# ap_hand_controller_v2.net
KiCad netlist of a schematic drawn in EAGLE
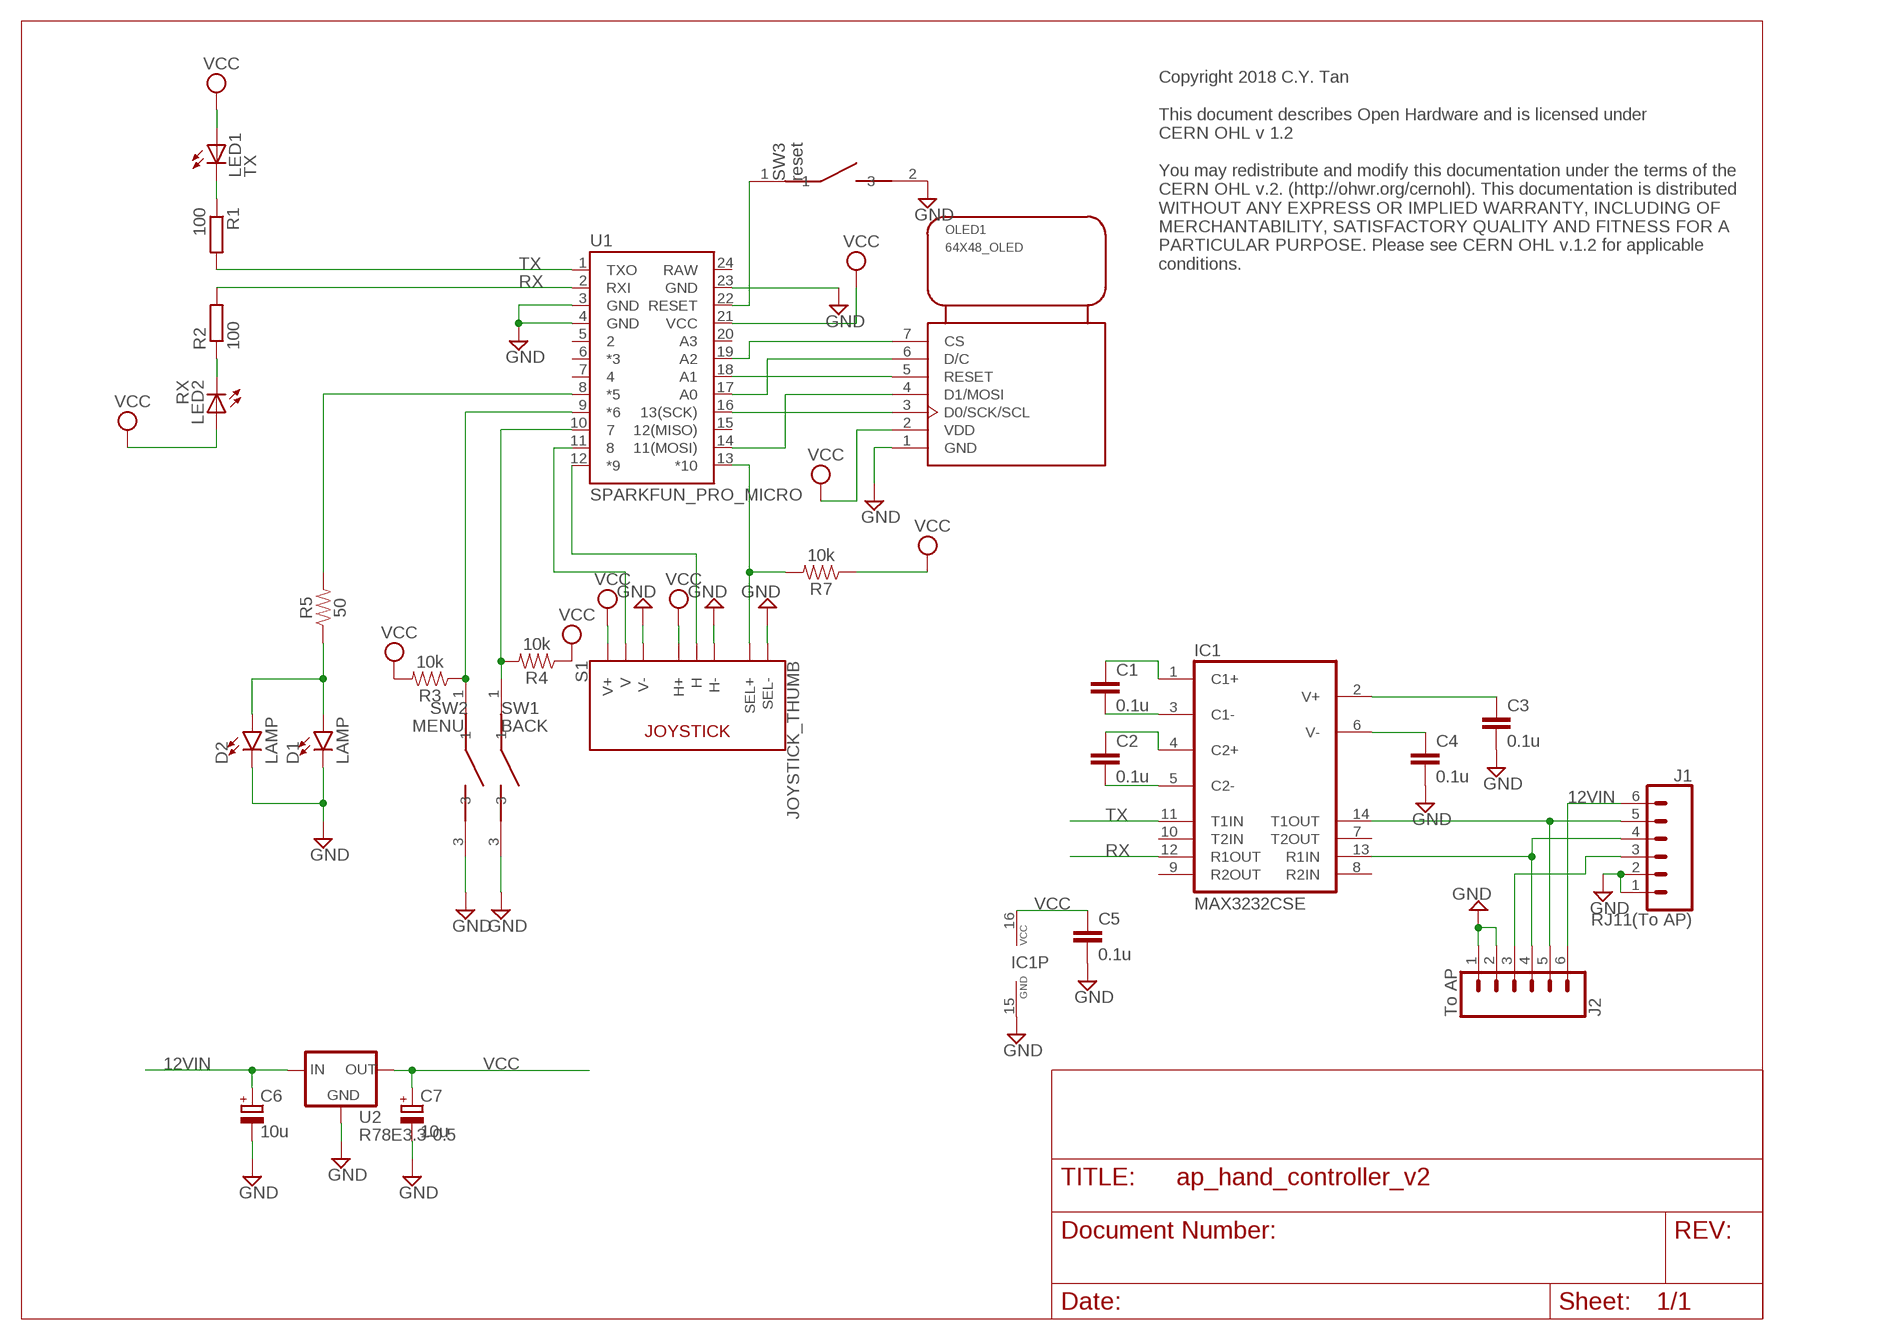
[diagram p0: schematic, sheet 1]

(export (version "E")
  (design (tool "Eeschema 10.0.6"))
  (components
    (comp (ref "C1")
      (value "0.1u")
      (footprint "eagle-import:C1206")
      (libsource (lib "eagle-import") (part "C-EUC1206"))
    )
    (comp (ref "C2")
      (value "0.1u")
      (footprint "eagle-import:C1206")
      (libsource (lib "eagle-import") (part "C-EUC1206"))
    )
    (comp (ref "C3")
      (value "0.1u")
      (footprint "eagle-import:C1206")
      (libsource (lib "eagle-import") (part "C-EUC1206"))
    )
    (comp (ref "C4")
      (value "0.1u")
      (footprint "eagle-import:C1206")
      (libsource (lib "eagle-import") (part "C-EUC1206"))
    )
    (comp (ref "C5")
      (value "0.1u")
      (footprint "eagle-import:C1206")
      (libsource (lib "eagle-import") (part "C-EUC1206"))
    )
    (comp (ref "C6")
      (value "10u")
      (footprint "eagle-import:E2,5-6")
      (libsource (lib "eagle-import") (part "CPOL-EUE2.5-6"))
    )
    (comp (ref "C7")
      (value "10u")
      (footprint "eagle-import:E2,5-6")
      (libsource (lib "eagle-import") (part "CPOL-EUE2.5-6"))
    )
    (comp (ref "D1")
      (value "LAMP")
      (footprint "eagle-import:LED_5MM")
      (libsource (lib "eagle-import") (part "LED5MM"))
    )
    (comp (ref "D2")
      (value "LAMP")
      (footprint "eagle-import:LED_5MM")
      (libsource (lib "eagle-import") (part "LED5MM"))
    )
    (comp (ref "IC1")
      (value "MAX3232CSE")
      (footprint "eagle-import:SO16")
      (libsource (lib "eagle-import") (part "MAX3232SEC"))
    )
    (comp (ref "J1")
      (value "RJ11(To AP)")
      (footprint "eagle-import:RJ11-6")
      (libsource (lib "eagle-import") (part "RJ11-6"))
    )
    (comp (ref "J2")
      (value "To AP")
      (footprint "eagle-import:1X06_NO_SILK")
      (libsource (lib "eagle-import") (part "CONN_06NO_SILK_FEMALE_PTH"))
    )
    (comp (ref "LED1")
      (value "TX")
      (footprint "eagle-import:CHIPLED_1206")
      (libsource (lib "eagle-import") (part "LEDCHIPLED_1206"))
    )
    (comp (ref "LED2")
      (value "RX")
      (footprint "eagle-import:CHIPLED_1206")
      (libsource (lib "eagle-import") (part "LEDCHIPLED_1206"))
    )
    (comp (ref "OLED1")
      (value "64X48_OLED")
      (footprint "eagle-import:64X48_OLED")
      (libsource (lib "eagle-import") (part "64X48_OLED"))
    )
    (comp (ref "R1")
      (value "100")
      (footprint "eagle-import:R0805")
      (libsource (lib "eagle-import") (part "R"))
    )
    (comp (ref "R2")
      (value "100")
      (footprint "eagle-import:R0805")
      (libsource (lib "eagle-import") (part "R"))
    )
    (comp (ref "R3")
      (value "10k")
      (footprint "eagle-import:AXIAL-0.3")
      (libsource (lib "eagle-import") (part "RESISTORAXIAL-0.3"))
    )
    (comp (ref "R4")
      (value "10k")
      (footprint "eagle-import:AXIAL-0.3")
      (libsource (lib "eagle-import") (part "RESISTORAXIAL-0.3"))
    )
    (comp (ref "R5")
      (value "50")
      (footprint "eagle-import:AXIAL-0.3")
      (libsource (lib "eagle-import") (part "RESISTORAXIAL-0.3"))
    )
    (comp (ref "R7")
      (value "10k")
      (footprint "eagle-import:AXIAL-0.3")
      (libsource (lib "eagle-import") (part "RESISTORAXIAL-0.3"))
    )
    (comp (ref "S1")
      (value "JOYSTICK_THUMB")
      (footprint "eagle-import:JOYSTICK")
      (libsource (lib "eagle-import") (part "JOYSTICK_THUMB"))
    )
    (comp (ref "SW1")
      (value "BACK")
      (footprint "eagle-import:TSA12110_TACT_SWITCH")
      (libsource (lib "eagle-import") (part "TSA12110_TACT_SWITCH"))
    )
    (comp (ref "SW2")
      (value "MENU")
      (footprint "eagle-import:TSA12110_TACT_SWITCH")
      (libsource (lib "eagle-import") (part "TSA12110_TACT_SWITCH"))
    )
    (comp (ref "SW3")
      (value "reset")
      (footprint "eagle-import:TACTILE_SWITCH_90DEG")
      (libsource (lib "eagle-import") (part "TACTILE_SWITCH_90DEG"))
    )
    (comp (ref "U1")
      (value "SPARKFUN_PRO_MICRO")
      (footprint "eagle-import:SPARKFUN_PRO_MICRO")
      (libsource (lib "eagle-import") (part "SPARKFUN_PRO_MICRO"))
    )
    (comp (ref "U2")
      (value "R78E3.3-0.5")
      (footprint "eagle-import:DC-DC_CONVERTER_78XX")
      (libsource (lib "eagle-import") (part "R-78E5.0-1.0"))
    )
  )
  (nets
    (net (code "1") (name "/12VIN") (class "Default")
      (node (ref "C6") (pin "+") (pinfunction "+_+") (pintype "passive"))
      (node (ref "J1") (pin "6") (pinfunction "6_6") (pintype "passive"))
      (node (ref "J2") (pin "6") (pinfunction "6_6") (pintype "passive"))
      (node (ref "U2") (pin "VIN") (pinfunction "IN_VIN") (pintype "input"))
    )
    (net (code "2") (name "/RAW") (class "Default")
      (node (ref "U1") (pin "24") (pinfunction "RAW_24") (pintype "power_in"))
    )
    (net (code "3") (name "/RX") (class "Default")
      (node (ref "IC1") (pin "12") (pinfunction "R1OUT_12") (pintype "output"))
      (node (ref "R2") (pin "2") (pinfunction "2_2") (pintype "passive"))
      (node (ref "U1") (pin "2") (pinfunction "RXI_2") (pintype "bidirectional"))
    )
    (net (code "4") (name "/TX") (class "Default")
      (node (ref "IC1") (pin "11") (pinfunction "T1IN_11") (pintype "input"))
      (node (ref "R1") (pin "2") (pinfunction "2_2") (pintype "passive"))
      (node (ref "U1") (pin "1") (pinfunction "TXO_1") (pintype "bidirectional"))
    )
    (net (code "5") (name "GND") (class "Default")
      (node (ref "C3") (pin "2") (pinfunction "2_2") (pintype "passive"))
      (node (ref "C4") (pin "2") (pinfunction "2_2") (pintype "passive"))
      (node (ref "C5") (pin "2") (pinfunction "2_2") (pintype "passive"))
      (node (ref "C6") (pin "-") (pinfunction "-_-") (pintype "passive"))
      (node (ref "C7") (pin "-") (pinfunction "-_-") (pintype "passive"))
      (node (ref "D1") (pin "K") (pinfunction "C_K") (pintype "passive"))
      (node (ref "D2") (pin "K") (pinfunction "C_K") (pintype "passive"))
      (node (ref "IC1") (pin "15") (pinfunction "GND_15") (pintype "power_in"))
      (node (ref "J1") (pin "1") (pinfunction "1_1") (pintype "passive"))
      (node (ref "J1") (pin "2") (pinfunction "2_2") (pintype "passive"))
      (node (ref "J2") (pin "1") (pinfunction "1_1") (pintype "passive"))
      (node (ref "J2") (pin "2") (pinfunction "2_2") (pintype "passive"))
      (node (ref "OLED1") (pin "1") (pinfunction "GND_1") (pintype "power_in"))
      (node (ref "S1") (pin "B2A") (pinfunction "SEL-_B2A") (pintype "bidirectional"))
      (node (ref "S1") (pin "H3") (pinfunction "H-_H3") (pintype "bidirectional"))
      (node (ref "S1") (pin "V3") (pinfunction "V-_V3") (pintype "bidirectional"))
      (node (ref "SW1") (pin "3") (pinfunction "3_3") (pintype "bidirectional"))
      (node (ref "SW2") (pin "3") (pinfunction "3_3") (pintype "bidirectional"))
      (node (ref "SW3") (pin "2") (pinfunction "3_2") (pintype "bidirectional"))
      (node (ref "U1") (pin "23") (pinfunction "GND_23") (pintype "power_in"))
      (node (ref "U1") (pin "3") (pinfunction "GND_3") (pintype "power_in"))
      (node (ref "U1") (pin "4") (pinfunction "GND_4") (pintype "power_in"))
      (node (ref "U2") (pin "GND") (pinfunction "GND_GND") (pintype "input"))
    )
    (net (code "6") (name "Net-(IC1A-C1+)") (class "Default")
      (node (ref "C1") (pin "1") (pinfunction "1_1") (pintype "passive"))
      (node (ref "IC1") (pin "1") (pinfunction "C1+_1") (pintype "bidirectional"))
    )
    (net (code "7") (name "Net-(IC1A-C1-)") (class "Default")
      (node (ref "C1") (pin "2") (pinfunction "2_2") (pintype "passive"))
      (node (ref "IC1") (pin "3") (pinfunction "C1-_3") (pintype "bidirectional"))
    )
    (net (code "8") (name "Net-(IC1A-C2+)") (class "Default")
      (node (ref "C2") (pin "1") (pinfunction "1_1") (pintype "passive"))
      (node (ref "IC1") (pin "4") (pinfunction "C2+_4") (pintype "bidirectional"))
    )
    (net (code "9") (name "Net-(IC1A-C2-)") (class "Default")
      (node (ref "C2") (pin "2") (pinfunction "2_2") (pintype "passive"))
      (node (ref "IC1") (pin "5") (pinfunction "C2-_5") (pintype "bidirectional"))
    )
    (net (code "10") (name "Net-(IC1A-R1IN)") (class "Default")
      (node (ref "IC1") (pin "13") (pinfunction "R1IN_13") (pintype "input"))
      (node (ref "J1") (pin "4") (pinfunction "4_4") (pintype "passive"))
      (node (ref "J2") (pin "4") (pinfunction "4_4") (pintype "passive"))
    )
    (net (code "11") (name "Net-(IC1A-T1OUT)") (class "Default")
      (node (ref "IC1") (pin "14") (pinfunction "T1OUT_14") (pintype "output"))
      (node (ref "J1") (pin "5") (pinfunction "5_5") (pintype "passive"))
      (node (ref "J2") (pin "5") (pinfunction "5_5") (pintype "passive"))
    )
    (net (code "12") (name "Net-(IC1A-V+)") (class "Default")
      (node (ref "C3") (pin "1") (pinfunction "1_1") (pintype "passive"))
      (node (ref "IC1") (pin "2") (pinfunction "V+_2") (pintype "bidirectional"))
    )
    (net (code "13") (name "Net-(IC1A-V-)") (class "Default")
      (node (ref "C4") (pin "1") (pinfunction "1_1") (pintype "passive"))
      (node (ref "IC1") (pin "6") (pinfunction "V-_6") (pintype "bidirectional"))
    )
    (net (code "14") (name "Net-(J1-Pad3)") (class "Default")
      (node (ref "J1") (pin "3") (pinfunction "3_3") (pintype "passive"))
      (node (ref "J2") (pin "3") (pinfunction "3_3") (pintype "passive"))
    )
    (net (code "15") (name "Net-(LED1-PadC)") (class "Default")
      (node (ref "LED1") (pin "C") (pinfunction "C_C") (pintype "passive"))
      (node (ref "R1") (pin "1") (pinfunction "1_1") (pintype "passive"))
    )
    (net (code "16") (name "Net-(LED2-PadC)") (class "Default")
      (node (ref "LED2") (pin "C") (pinfunction "C_C") (pintype "passive"))
      (node (ref "R2") (pin "1") (pinfunction "1_1") (pintype "passive"))
    )
    (net (code "17") (name "Net-(OLED1-CS)") (class "Default")
      (node (ref "OLED1") (pin "7") (pinfunction "CS_7") (pintype "input"))
      (node (ref "U1") (pin "19") (pinfunction "A2_19") (pintype "bidirectional"))
    )
    (net (code "18") (name "Net-(OLED1-D0{slash}SCK{slash}SCL)") (class "Default")
      (node (ref "OLED1") (pin "3") (pinfunction "D0/SCK/SCL_3") (pintype "input"))
      (node (ref "U1") (pin "16") (pinfunction "13(SCK)_16") (pintype "bidirectional"))
    )
    (net (code "19") (name "Net-(OLED1-D1{slash}MOSI)") (class "Default")
      (node (ref "OLED1") (pin "4") (pinfunction "D1/MOSI_4") (pintype "bidirectional"))
      (node (ref "U1") (pin "14") (pinfunction "11(MOSI)_14") (pintype "bidirectional"))
    )
    (net (code "20") (name "Net-(OLED1-D{slash}C)") (class "Default")
      (node (ref "OLED1") (pin "6") (pinfunction "D/C_6") (pintype "bidirectional"))
      (node (ref "U1") (pin "17") (pinfunction "A0_17") (pintype "bidirectional"))
    )
    (net (code "21") (name "Net-(OLED1-RESET)") (class "Default")
      (node (ref "OLED1") (pin "5") (pinfunction "RESET_5") (pintype "input"))
      (node (ref "U1") (pin "18") (pinfunction "A1_18") (pintype "bidirectional"))
    )
    (net (code "22") (name "Net-(R3-1)") (class "Default")
      (node (ref "R3") (pin "P$1") (pinfunction "1_P$1") (pintype "passive"))
      (node (ref "SW2") (pin "1") (pinfunction "1_1") (pintype "bidirectional"))
      (node (ref "U1") (pin "9") (pinfunction "*6_9") (pintype "bidirectional"))
    )
    (net (code "23") (name "Net-(R4-2)") (class "Default")
      (node (ref "R4") (pin "P$2") (pinfunction "2_P$2") (pintype "passive"))
      (node (ref "SW1") (pin "1") (pinfunction "1_1") (pintype "bidirectional"))
      (node (ref "U1") (pin "10") (pinfunction "7_10") (pintype "bidirectional"))
    )
    (net (code "24") (name "Net-(R5-1)") (class "Default")
      (node (ref "D1") (pin "A") (pinfunction "A_A") (pintype "passive"))
      (node (ref "D2") (pin "A") (pinfunction "A_A") (pintype "passive"))
      (node (ref "R5") (pin "P$1") (pinfunction "1_P$1") (pintype "passive"))
    )
    (net (code "25") (name "Net-(R5-2)") (class "Default")
      (node (ref "R5") (pin "P$2") (pinfunction "2_P$2") (pintype "passive"))
      (node (ref "U1") (pin "8") (pinfunction "*5_8") (pintype "bidirectional"))
    )
    (net (code "26") (name "Net-(R7-2)") (class "Default")
      (node (ref "R7") (pin "P$2") (pinfunction "2_P$2") (pintype "passive"))
      (node (ref "S1") (pin "B1A") (pinfunction "SEL+_B1A") (pintype "bidirectional"))
      (node (ref "U1") (pin "13") (pinfunction "*10_13") (pintype "bidirectional"))
    )
    (net (code "27") (name "Net-(S1-H)") (class "Default")
      (node (ref "S1") (pin "H2") (pinfunction "H_H2") (pintype "bidirectional"))
      (node (ref "U1") (pin "12") (pinfunction "*9_12") (pintype "bidirectional"))
    )
    (net (code "28") (name "Net-(S1-V)") (class "Default")
      (node (ref "S1") (pin "V2") (pinfunction "V_V2") (pintype "bidirectional"))
      (node (ref "U1") (pin "11") (pinfunction "8_11") (pintype "bidirectional"))
    )
    (net (code "29") (name "Net-(U1-RESET)") (class "Default")
      (node (ref "SW3") (pin "1") (pinfunction "1_1") (pintype "bidirectional"))
      (node (ref "U1") (pin "22") (pinfunction "RESET_22") (pintype "bidirectional"))
    )
    (net (code "30") (name "VCC") (class "Default")
      (node (ref "C5") (pin "1") (pinfunction "1_1") (pintype "passive"))
      (node (ref "C7") (pin "+") (pinfunction "+_+") (pintype "passive"))
      (node (ref "IC1") (pin "16") (pinfunction "VCC_16") (pintype "power_in"))
      (node (ref "LED1") (pin "A") (pinfunction "A_A") (pintype "passive"))
      (node (ref "LED2") (pin "A") (pinfunction "A_A") (pintype "passive"))
      (node (ref "OLED1") (pin "2") (pinfunction "VDD_2") (pintype "power_in"))
      (node (ref "R3") (pin "P$2") (pinfunction "2_P$2") (pintype "passive"))
      (node (ref "R4") (pin "P$1") (pinfunction "1_P$1") (pintype "passive"))
      (node (ref "R7") (pin "P$1") (pinfunction "1_P$1") (pintype "passive"))
      (node (ref "S1") (pin "H1") (pinfunction "H+_H1") (pintype "bidirectional"))
      (node (ref "S1") (pin "V1") (pinfunction "V+_V1") (pintype "bidirectional"))
      (node (ref "U1") (pin "21") (pinfunction "VCC_21") (pintype "power_in"))
      (node (ref "U2") (pin "VOUT") (pinfunction "OUT_VOUT") (pintype "passive"))
    )
    (net (code "31") (name "unconnected-(IC1A-R2IN-Pad8)") (class "Default")
      (node (ref "IC1") (pin "8") (pinfunction "R2IN_8") (pintype "input"))
    )
    (net (code "32") (name "unconnected-(IC1A-R2OUT-Pad9)") (class "Default")
      (node (ref "IC1") (pin "9") (pinfunction "R2OUT_9") (pintype "output"))
    )
    (net (code "33") (name "unconnected-(IC1A-T2IN-Pad10)") (class "Default")
      (node (ref "IC1") (pin "10") (pinfunction "T2IN_10") (pintype "input"))
    )
    (net (code "34") (name "unconnected-(IC1A-T2OUT-Pad7)") (class "Default")
      (node (ref "IC1") (pin "7") (pinfunction "T2OUT_7") (pintype "output"))
    )
    (net (code "35") (name "unconnected-(U1-*3-Pad6)") (class "Default")
      (node (ref "U1") (pin "6") (pinfunction "*3_6") (pintype "bidirectional"))
    )
    (net (code "36") (name "unconnected-(U1-2-Pad5)") (class "Default")
      (node (ref "U1") (pin "5") (pinfunction "2_5") (pintype "bidirectional"))
    )
    (net (code "37") (name "unconnected-(U1-4-Pad7)") (class "Default")
      (node (ref "U1") (pin "7") (pinfunction "4_7") (pintype "bidirectional"))
    )
    (net (code "38") (name "unconnected-(U1-12(MISO)-Pad15)") (class "Default")
      (node (ref "U1") (pin "15") (pinfunction "12(MISO)_15") (pintype "bidirectional"))
    )
    (net (code "39") (name "unconnected-(U1-A3-Pad20)") (class "Default")
      (node (ref "U1") (pin "20") (pinfunction "A3_20") (pintype "bidirectional"))
    )
  )
)
